# LED.net
KiCad netlist of a schematic drawn in EAGLE
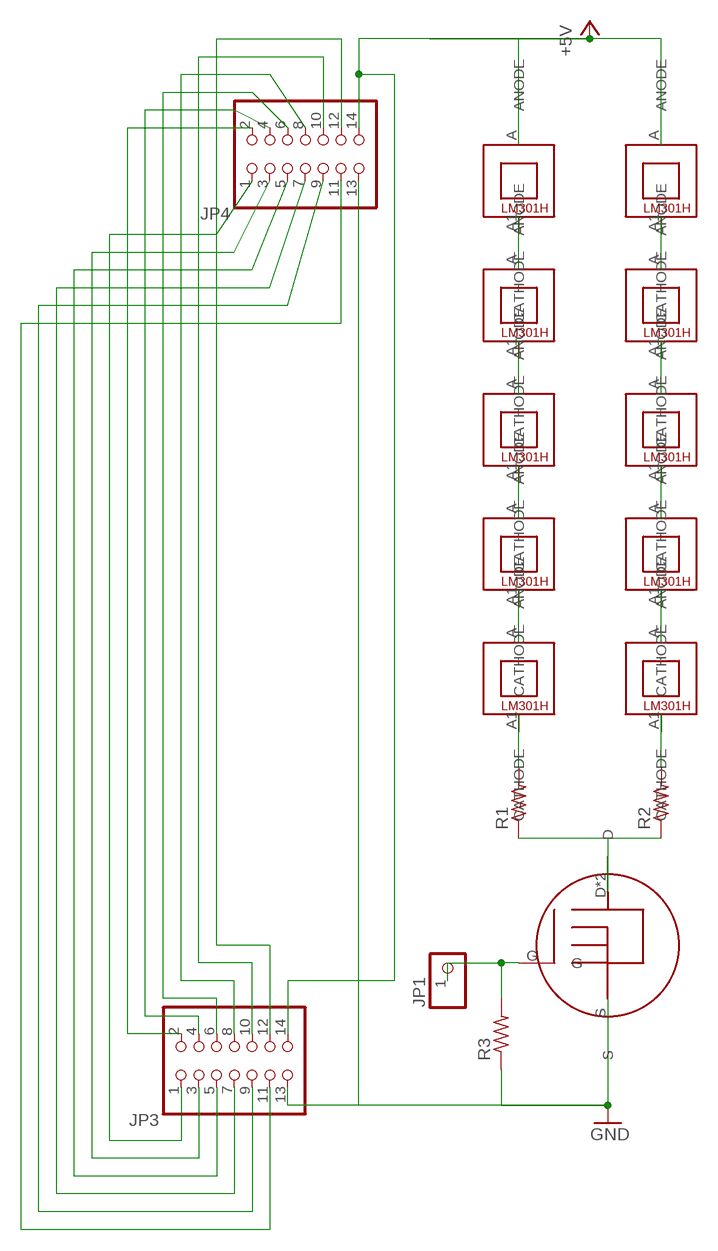
[diagram p0: schematic, sheet 1]

(export (version "E")
  (design (tool "Eeschema 10.0.6"))
  (components
    (comp (ref "JP1")
      (value "PINHD-1X1")
      (footprint "eagle-import:1X01")
      (libsource (lib "eagle-import") (part "PINHD-1X1"))
    )
    (comp (ref "JP3")
      (value "PINHD-2X7")
      (footprint "eagle-import:2X07")
      (libsource (lib "eagle-import") (part "PINHD-2X7"))
    )
    (comp (ref "JP4")
      (value "PINHD-2X7")
      (footprint "eagle-import:2X07")
      (libsource (lib "eagle-import") (part "PINHD-2X7"))
    )
    (comp (ref "R1")
      (value "FLIPFLOP-RES")
      (footprint "eagle-import:0805-THM")
      (libsource (lib "eagle-import") (part "FLIPFLOP-RES"))
    )
    (comp (ref "R2")
      (value "FLIPFLOP-RES")
      (footprint "eagle-import:0805-THM")
      (libsource (lib "eagle-import") (part "FLIPFLOP-RES"))
    )
    (comp (ref "R3")
      (value "FLIPFLOP-RES")
      (footprint "eagle-import:0805-THM")
      (libsource (lib "eagle-import") (part "FLIPFLOP-RES"))
    )
    (comp (ref "U$1")
      (value "LM301H")
      (footprint "eagle-import:SPMWHD32AMH5XAT5SL")
      (libsource (lib "eagle-import") (part "LM301H"))
    )
    (comp (ref "U$2")
      (value "LM301H")
      (footprint "eagle-import:SPMWHD32AMH5XAT5SL")
      (libsource (lib "eagle-import") (part "LM301H"))
    )
    (comp (ref "U$3")
      (value "LM301H")
      (footprint "eagle-import:SPMWHD32AMH5XAT5SL")
      (libsource (lib "eagle-import") (part "LM301H"))
    )
    (comp (ref "U$4")
      (value "LM301H")
      (footprint "eagle-import:SPMWHD32AMH5XAT5SL")
      (libsource (lib "eagle-import") (part "LM301H"))
    )
    (comp (ref "U$5")
      (value "LM301H")
      (footprint "eagle-import:SPMWHD32AMH5XAT5SL")
      (libsource (lib "eagle-import") (part "LM301H"))
    )
    (comp (ref "U$6")
      (value "LM301H")
      (footprint "eagle-import:SPMWHD32AMH5XAT5SL")
      (libsource (lib "eagle-import") (part "LM301H"))
    )
    (comp (ref "U$7")
      (value "LM301H")
      (footprint "eagle-import:SPMWHD32AMH5XAT5SL")
      (libsource (lib "eagle-import") (part "LM301H"))
    )
    (comp (ref "U$8")
      (value "LM301H")
      (footprint "eagle-import:SPMWHD32AMH5XAT5SL")
      (libsource (lib "eagle-import") (part "LM301H"))
    )
    (comp (ref "U$9")
      (value "LM301H")
      (footprint "eagle-import:SPMWHD32AMH5XAT5SL")
      (libsource (lib "eagle-import") (part "LM301H"))
    )
    (comp (ref "U$10")
      (value "LM301H")
      (footprint "eagle-import:SPMWHD32AMH5XAT5SL")
      (libsource (lib "eagle-import") (part "LM301H"))
    )
    (comp (ref "U$11")
      (value "SOT223")
      (footprint "eagle-import:S")
      (libsource (lib "eagle-import") (part "SOT223"))
    )
  )
  (nets
    (net (code "1") (name "+5V") (class "Default")
      (node (ref "JP3") (pin "14") (pinfunction "14_14") (pintype "passive"))
      (node (ref "JP4") (pin "14") (pinfunction "14_14") (pintype "passive"))
      (node (ref "U$1") (pin "A") (pinfunction "ANODE_A") (pintype "bidirectional"))
      (node (ref "U$6") (pin "A") (pinfunction "ANODE_A") (pintype "bidirectional"))
    )
    (net (code "2") (name "GND") (class "Default")
      (node (ref "JP3") (pin "13") (pinfunction "13_13") (pintype "passive"))
      (node (ref "JP4") (pin "13") (pinfunction "13_13") (pintype "passive"))
      (node (ref "R3") (pin "1") (pinfunction "1_1") (pintype "passive"))
      (node (ref "U$11") (pin "S") (pinfunction "S_S") (pintype "bidirectional"))
    )
    (net (code "3") (name "Net-(JP1-Pad1)") (class "Default")
      (node (ref "JP1") (pin "1") (pinfunction "1_1") (pintype "passive"))
      (node (ref "R3") (pin "2") (pinfunction "2_2") (pintype "passive"))
      (node (ref "U$11") (pin "G") (pinfunction "G_G") (pintype "bidirectional"))
    )
    (net (code "4") (name "Net-(JP3-Pad1)") (class "Default")
      (node (ref "JP3") (pin "1") (pinfunction "1_1") (pintype "passive"))
      (node (ref "JP4") (pin "1") (pinfunction "1_1") (pintype "passive"))
    )
    (net (code "5") (name "Net-(JP3-Pad2)") (class "Default")
      (node (ref "JP3") (pin "2") (pinfunction "2_2") (pintype "passive"))
      (node (ref "JP4") (pin "2") (pinfunction "2_2") (pintype "passive"))
    )
    (net (code "6") (name "Net-(JP3-Pad3)") (class "Default")
      (node (ref "JP3") (pin "3") (pinfunction "3_3") (pintype "passive"))
      (node (ref "JP4") (pin "3") (pinfunction "3_3") (pintype "passive"))
    )
    (net (code "7") (name "Net-(JP3-Pad4)") (class "Default")
      (node (ref "JP3") (pin "4") (pinfunction "4_4") (pintype "passive"))
      (node (ref "JP4") (pin "4") (pinfunction "4_4") (pintype "passive"))
    )
    (net (code "8") (name "Net-(JP3-Pad5)") (class "Default")
      (node (ref "JP3") (pin "5") (pinfunction "5_5") (pintype "passive"))
      (node (ref "JP4") (pin "5") (pinfunction "5_5") (pintype "passive"))
    )
    (net (code "9") (name "Net-(JP3-Pad6)") (class "Default")
      (node (ref "JP3") (pin "6") (pinfunction "6_6") (pintype "passive"))
      (node (ref "JP4") (pin "6") (pinfunction "6_6") (pintype "passive"))
    )
    (net (code "10") (name "Net-(JP3-Pad7)") (class "Default")
      (node (ref "JP3") (pin "7") (pinfunction "7_7") (pintype "passive"))
      (node (ref "JP4") (pin "7") (pinfunction "7_7") (pintype "passive"))
    )
    (net (code "11") (name "Net-(JP3-Pad8)") (class "Default")
      (node (ref "JP3") (pin "8") (pinfunction "8_8") (pintype "passive"))
      (node (ref "JP4") (pin "8") (pinfunction "8_8") (pintype "passive"))
    )
    (net (code "12") (name "Net-(JP3-Pad9)") (class "Default")
      (node (ref "JP3") (pin "9") (pinfunction "9_9") (pintype "passive"))
      (node (ref "JP4") (pin "9") (pinfunction "9_9") (pintype "passive"))
    )
    (net (code "13") (name "Net-(JP3-Pad10)") (class "Default")
      (node (ref "JP3") (pin "10") (pinfunction "10_10") (pintype "passive"))
      (node (ref "JP4") (pin "10") (pinfunction "10_10") (pintype "passive"))
    )
    (net (code "14") (name "Net-(JP3-Pad11)") (class "Default")
      (node (ref "JP3") (pin "11") (pinfunction "11_11") (pintype "passive"))
      (node (ref "JP4") (pin "11") (pinfunction "11_11") (pintype "passive"))
    )
    (net (code "15") (name "Net-(JP3-Pad12)") (class "Default")
      (node (ref "JP3") (pin "12") (pinfunction "12_12") (pintype "passive"))
      (node (ref "JP4") (pin "12") (pinfunction "12_12") (pintype "passive"))
    )
    (net (code "16") (name "Net-(R1-Pad1)") (class "Default")
      (node (ref "R1") (pin "1") (pinfunction "1_1") (pintype "passive"))
      (node (ref "R2") (pin "1") (pinfunction "1_1") (pintype "passive"))
      (node (ref "U$11") (pin "D") (pinfunction "D_D") (pintype "bidirectional"))
      (node (ref "U$11") (pin "DKLEIN") (pinfunction "D_DKLEIN") (pintype "bidirectional"))
    )
    (net (code "17") (name "Net-(U$1-CATHODE)") (class "Default")
      (node (ref "U$1") (pin "A1") (pinfunction "CATHODE_A1") (pintype "bidirectional"))
      (node (ref "U$2") (pin "A") (pinfunction "ANODE_A") (pintype "bidirectional"))
    )
    (net (code "18") (name "Net-(U$2-CATHODE)") (class "Default")
      (node (ref "U$2") (pin "A1") (pinfunction "CATHODE_A1") (pintype "bidirectional"))
      (node (ref "U$3") (pin "A") (pinfunction "ANODE_A") (pintype "bidirectional"))
    )
    (net (code "19") (name "Net-(U$3-CATHODE)") (class "Default")
      (node (ref "U$3") (pin "A1") (pinfunction "CATHODE_A1") (pintype "bidirectional"))
      (node (ref "U$4") (pin "A") (pinfunction "ANODE_A") (pintype "bidirectional"))
    )
    (net (code "20") (name "Net-(U$4-CATHODE)") (class "Default")
      (node (ref "U$4") (pin "A1") (pinfunction "CATHODE_A1") (pintype "bidirectional"))
      (node (ref "U$5") (pin "A") (pinfunction "ANODE_A") (pintype "bidirectional"))
    )
    (net (code "21") (name "Net-(U$5-CATHODE)") (class "Default")
      (node (ref "R1") (pin "2") (pinfunction "2_2") (pintype "passive"))
      (node (ref "U$5") (pin "A1") (pinfunction "CATHODE_A1") (pintype "bidirectional"))
    )
    (net (code "22") (name "Net-(U$6-CATHODE)") (class "Default")
      (node (ref "U$6") (pin "A1") (pinfunction "CATHODE_A1") (pintype "bidirectional"))
      (node (ref "U$7") (pin "A") (pinfunction "ANODE_A") (pintype "bidirectional"))
    )
    (net (code "23") (name "Net-(U$7-CATHODE)") (class "Default")
      (node (ref "U$7") (pin "A1") (pinfunction "CATHODE_A1") (pintype "bidirectional"))
      (node (ref "U$8") (pin "A") (pinfunction "ANODE_A") (pintype "bidirectional"))
    )
    (net (code "24") (name "Net-(U$8-CATHODE)") (class "Default")
      (node (ref "U$8") (pin "A1") (pinfunction "CATHODE_A1") (pintype "bidirectional"))
      (node (ref "U$9") (pin "A") (pinfunction "ANODE_A") (pintype "bidirectional"))
    )
    (net (code "25") (name "Net-(U$10-ANODE)") (class "Default")
      (node (ref "U$10") (pin "A") (pinfunction "ANODE_A") (pintype "bidirectional"))
      (node (ref "U$9") (pin "A1") (pinfunction "CATHODE_A1") (pintype "bidirectional"))
    )
    (net (code "26") (name "Net-(U$10-CATHODE)") (class "Default")
      (node (ref "R2") (pin "2") (pinfunction "2_2") (pintype "passive"))
      (node (ref "U$10") (pin "A1") (pinfunction "CATHODE_A1") (pintype "bidirectional"))
    )
  )
)
